# armor_schematic_std.net
KiCad netlist of a schematic drawn in EasyEDA
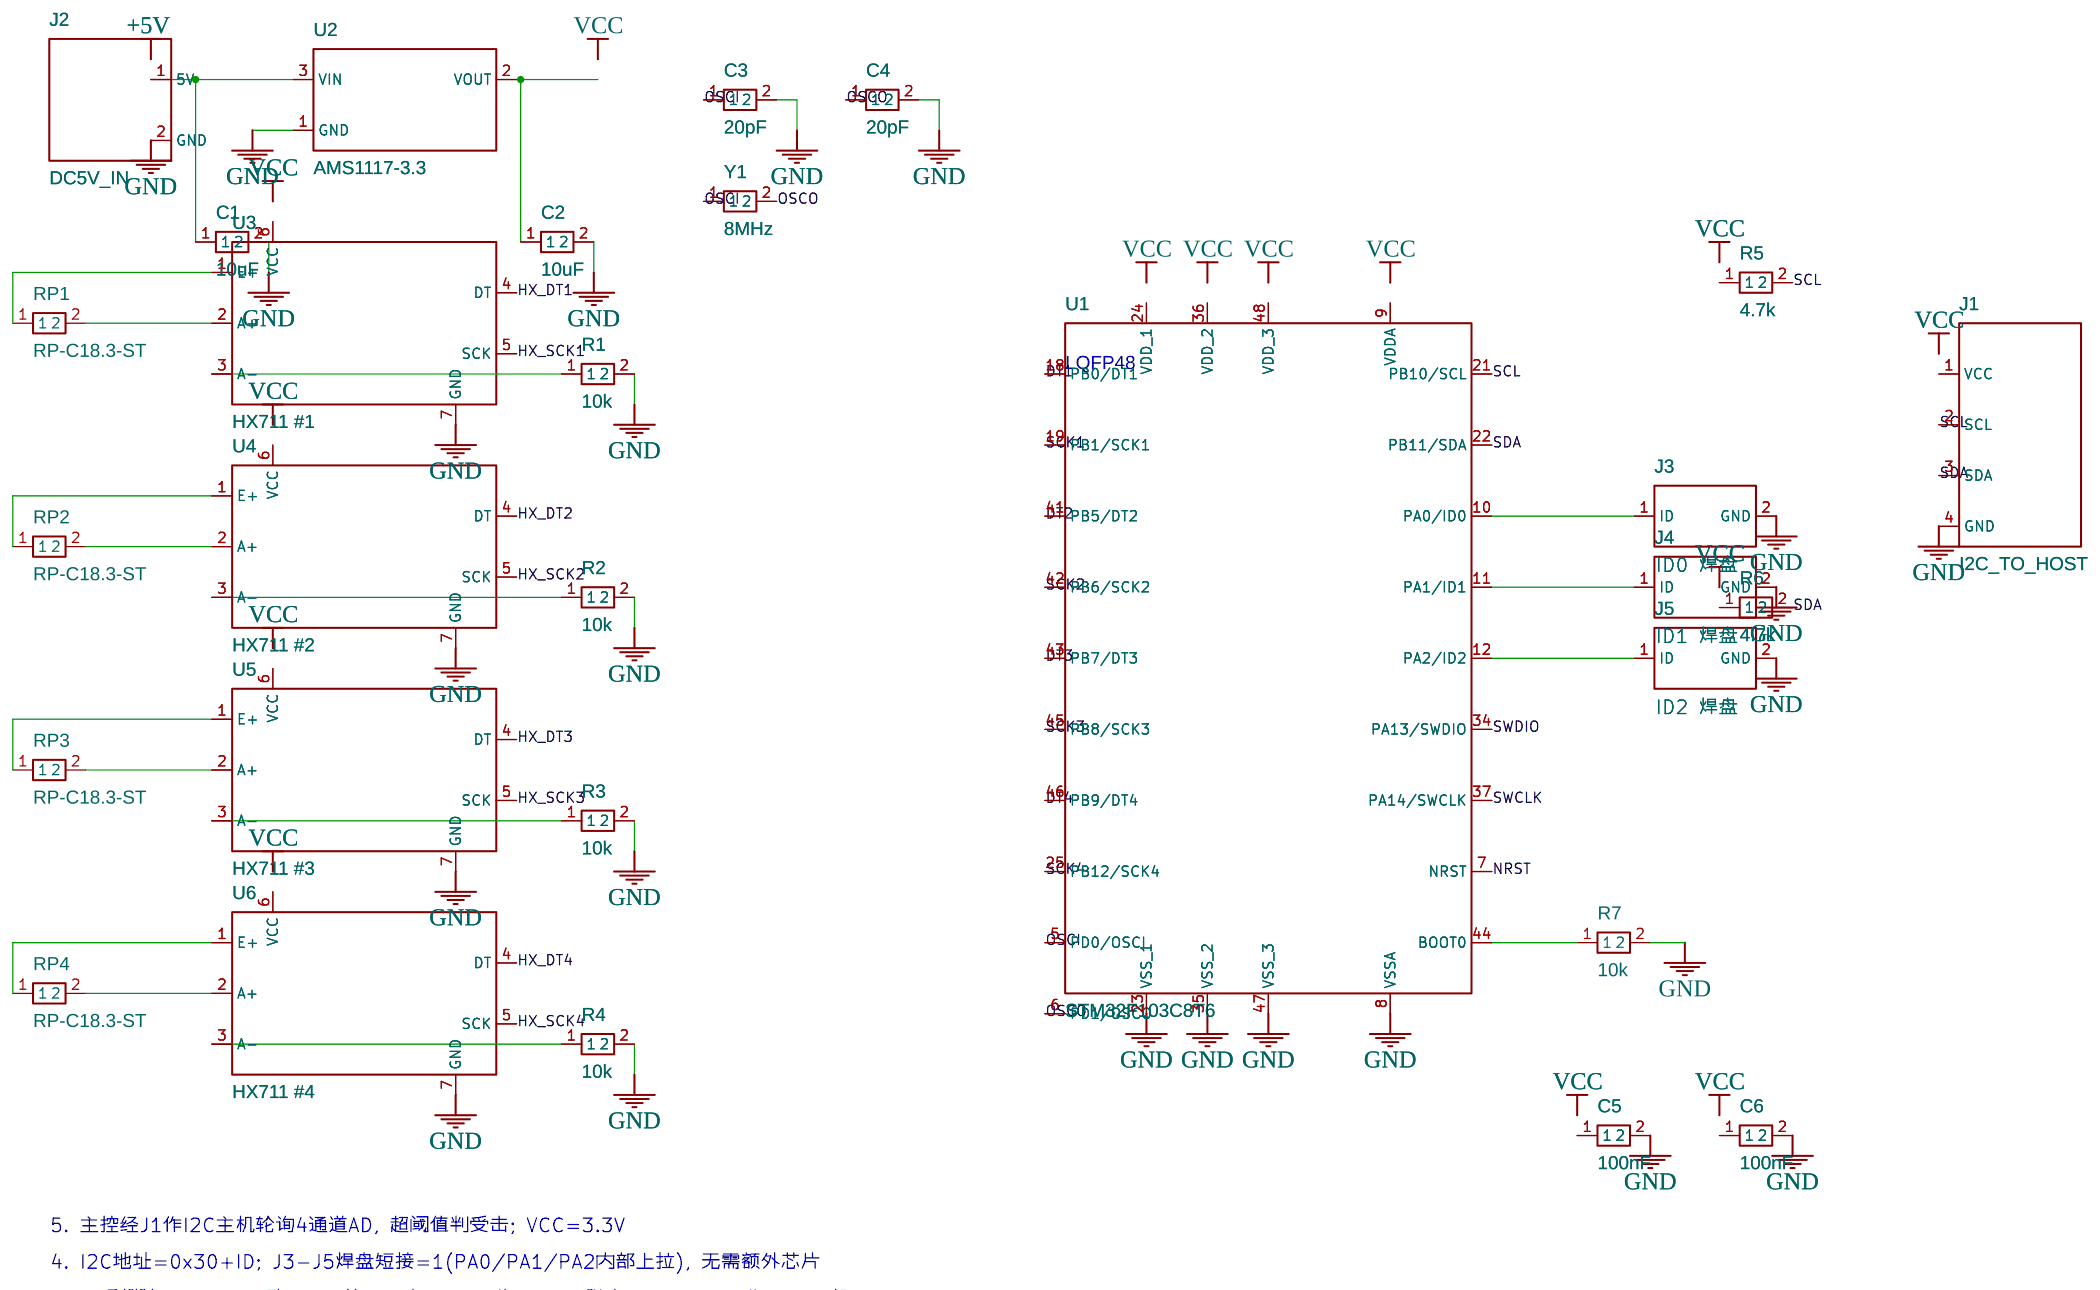
[diagram p0: schematic sheet]

(export (version "E")
  (design (tool "Eeschema 10.0.6"))
  (components
    (comp (ref "C1")
      (value "10uF")
      (fields (field (name "BOM_Manufacturer Part") "CL21A106KAYNNNE"))
      (libsource (lib "") (part "10uF"))
    )
    (comp (ref "C2")
      (value "10uF")
      (fields (field (name "BOM_Manufacturer Part") "CL21A106KAYNNNE"))
      (libsource (lib "") (part "10uF"))
    )
    (comp (ref "C3")
      (value "20pF")
      (fields (field (name "BOM_Manufacturer Part") "CL10C200JB8NNNC"))
      (libsource (lib "") (part "20pF"))
    )
    (comp (ref "C4")
      (value "20pF")
      (fields (field (name "BOM_Manufacturer Part") "CL10C200JB8NNNC"))
      (libsource (lib "") (part "20pF"))
    )
    (comp (ref "C5")
      (value "100nF")
      (fields (field (name "BOM_Manufacturer Part") "CC0603KRX7R9BB104"))
      (libsource (lib "") (part "100nF"))
    )
    (comp (ref "C6")
      (value "100nF")
      (fields (field (name "BOM_Manufacturer Part") "CC0603KRX7R9BB104"))
      (libsource (lib "") (part "100nF"))
    )
    (comp (ref "J1")
      (value "I2C_TO_HOST")
      (fields (field (name "BOM_Manufacturer Part") "PZ254V-11-04P"))
      (libsource (lib "") (part "I2C_TO_HOST"))
    )
    (comp (ref "J2")
      (value "DC5V_IN")
      (fields (field (name "BOM_Manufacturer Part") "PZ254V-11-02P"))
      (libsource (lib "") (part "DC5V_IN"))
    )
    (comp (ref "J3")
      (value "ID0 焊盘")
      (fields (field (name "BOM_Manufacturer Part") "PZ254V-11-02P"))
      (libsource (lib "") (part "ID0 焊盘"))
    )
    (comp (ref "J4")
      (value "ID1 焊盘")
      (fields (field (name "BOM_Manufacturer Part") "PZ254V-11-02P"))
      (libsource (lib "") (part "ID1 焊盘"))
    )
    (comp (ref "J5")
      (value "ID2 焊盘")
      (fields (field (name "BOM_Manufacturer Part") "PZ254V-11-02P"))
      (libsource (lib "") (part "ID2 焊盘"))
    )
    (comp (ref "R1")
      (value "10k")
      (fields (field (name "BOM_Manufacturer Part") "0603WAF1002T5E"))
      (libsource (lib "") (part "10k"))
    )
    (comp (ref "R2")
      (value "10k")
      (fields (field (name "BOM_Manufacturer Part") "0603WAF1002T5E"))
      (libsource (lib "") (part "10k"))
    )
    (comp (ref "R3")
      (value "10k")
      (fields (field (name "BOM_Manufacturer Part") "0603WAF1002T5E"))
      (libsource (lib "") (part "10k"))
    )
    (comp (ref "R4")
      (value "10k")
      (fields (field (name "BOM_Manufacturer Part") "0603WAF1002T5E"))
      (libsource (lib "") (part "10k"))
    )
    (comp (ref "R5")
      (value "4.7k")
      (fields (field (name "BOM_Manufacturer Part") "0603WAF4701T5E"))
      (libsource (lib "") (part "4.7k"))
    )
    (comp (ref "R6")
      (value "4.7k")
      (fields (field (name "BOM_Manufacturer Part") "0603WAF4701T5E"))
      (libsource (lib "") (part "4.7k"))
    )
    (comp (ref "R7")
      (value "10k")
      (fields (field (name "BOM_Manufacturer Part") "0603WAF1002T5E"))
      (libsource (lib "") (part "10k"))
    )
    (comp (ref "RP1") (value "RP-C18.3-ST") (libsource (lib "") (part "RP-C18.3-ST")))
    (comp (ref "RP2") (value "RP-C18.3-ST") (libsource (lib "") (part "RP-C18.3-ST")))
    (comp (ref "RP3") (value "RP-C18.3-ST") (libsource (lib "") (part "RP-C18.3-ST")))
    (comp (ref "RP4") (value "RP-C18.3-ST") (libsource (lib "") (part "RP-C18.3-ST")))
    (comp (ref "U1") (value "STM32F103C8T6") (libsource (lib "") (part "STM32F103C8T6")))
    (comp (ref "U2") (value "AMS1117-3.3") (libsource (lib "") (part "AMS1117-3.3")))
    (comp (ref "U3")
      (value "HX711 #1")
      (fields (field (name "BOM_Manufacturer Part") "HX711 module"))
      (libsource (lib "") (part "HX711 #1"))
    )
    (comp (ref "U4")
      (value "HX711 #2")
      (fields (field (name "BOM_Manufacturer Part") "HX711 module"))
      (libsource (lib "") (part "HX711 #2"))
    )
    (comp (ref "U5")
      (value "HX711 #3")
      (fields (field (name "BOM_Manufacturer Part") "HX711 module"))
      (libsource (lib "") (part "HX711 #3"))
    )
    (comp (ref "U6")
      (value "HX711 #4")
      (fields (field (name "BOM_Manufacturer Part") "HX711 module"))
      (libsource (lib "") (part "HX711 #4"))
    )
    (comp (ref "Y1")
      (value "8MHz")
      (fields (field (name "BOM_Manufacturer Part") "7U08000E10UCG"))
      (libsource (lib "") (part "8MHz"))
    )
  )
  (nets
    (net (code "2") (name "/DT1") (class "Default")
      (node (ref "U1") (pin "18") (pinfunction "PB0/DT1_18") (pintype "unspecified"))
    )
    (net (code "3") (name "/DT2") (class "Default")
      (node (ref "U1") (pin "41") (pinfunction "PB5/DT2_41") (pintype "unspecified"))
    )
    (net (code "4") (name "/DT3") (class "Default")
      (node (ref "U1") (pin "43") (pinfunction "PB7/DT3_43") (pintype "unspecified"))
    )
    (net (code "5") (name "/DT4") (class "Default")
      (node (ref "U1") (pin "46") (pinfunction "PB9/DT4_46") (pintype "unspecified"))
    )
    (net (code "6") (name "/HX_DT1") (class "Default")
      (node (ref "U3") (pin "4") (pinfunction "DT_4") (pintype "unspecified"))
    )
    (net (code "7") (name "/HX_DT2") (class "Default")
      (node (ref "U4") (pin "4") (pinfunction "DT_4") (pintype "unspecified"))
    )
    (net (code "8") (name "/HX_DT3") (class "Default")
      (node (ref "U5") (pin "4") (pinfunction "DT_4") (pintype "unspecified"))
    )
    (net (code "9") (name "/HX_DT4") (class "Default")
      (node (ref "U6") (pin "4") (pinfunction "DT_4") (pintype "unspecified"))
    )
    (net (code "10") (name "/HX_SCK1") (class "Default")
      (node (ref "U3") (pin "5") (pinfunction "SCK_5") (pintype "unspecified"))
    )
    (net (code "11") (name "/HX_SCK2") (class "Default")
      (node (ref "U4") (pin "5") (pinfunction "SCK_5") (pintype "unspecified"))
    )
    (net (code "12") (name "/HX_SCK3") (class "Default")
      (node (ref "U5") (pin "5") (pinfunction "SCK_5") (pintype "unspecified"))
    )
    (net (code "13") (name "/HX_SCK4") (class "Default")
      (node (ref "U6") (pin "5") (pinfunction "SCK_5") (pintype "unspecified"))
    )
    (net (code "14") (name "/NRST") (class "Default")
      (node (ref "U1") (pin "7") (pinfunction "NRST_7") (pintype "unspecified"))
    )
    (net (code "15") (name "/OSCI") (class "Default")
      (node (ref "C3") (pin "1") (pinfunction "1_1") (pintype "unspecified"))
      (node (ref "U1") (pin "5") (pinfunction "PD0/OSCI_5") (pintype "unspecified"))
      (node (ref "Y1") (pin "1") (pinfunction "1_1") (pintype "unspecified"))
    )
    (net (code "16") (name "/OSCO") (class "Default")
      (node (ref "C4") (pin "1") (pinfunction "1_1") (pintype "unspecified"))
      (node (ref "U1") (pin "6") (pinfunction "PD1/OSCO_6") (pintype "unspecified"))
      (node (ref "Y1") (pin "2") (pinfunction "2_2") (pintype "unspecified"))
    )
    (net (code "17") (name "/SCK1") (class "Default")
      (node (ref "U1") (pin "19") (pinfunction "PB1/SCK1_19") (pintype "unspecified"))
    )
    (net (code "18") (name "/SCK2") (class "Default")
      (node (ref "U1") (pin "42") (pinfunction "PB6/SCK2_42") (pintype "unspecified"))
    )
    (net (code "19") (name "/SCK3") (class "Default")
      (node (ref "U1") (pin "45") (pinfunction "PB8/SCK3_45") (pintype "unspecified"))
    )
    (net (code "20") (name "/SCK4") (class "Default")
      (node (ref "U1") (pin "25") (pinfunction "PB12/SCK4_25") (pintype "unspecified"))
    )
    (net (code "21") (name "/SCL") (class "Default")
      (node (ref "J1") (pin "2") (pinfunction "SCL_2") (pintype "unspecified"))
      (node (ref "R5") (pin "2") (pinfunction "2_2") (pintype "unspecified"))
      (node (ref "U1") (pin "21") (pinfunction "PB10/SCL_21") (pintype "unspecified"))
    )
    (net (code "22") (name "/SDA") (class "Default")
      (node (ref "J1") (pin "3") (pinfunction "SDA_3") (pintype "unspecified"))
      (node (ref "R6") (pin "2") (pinfunction "2_2") (pintype "unspecified"))
      (node (ref "U1") (pin "22") (pinfunction "PB11/SDA_22") (pintype "unspecified"))
    )
    (net (code "23") (name "/SWCLK") (class "Default")
      (node (ref "U1") (pin "37") (pinfunction "PA14/SWCLK_37") (pintype "unspecified"))
    )
    (net (code "24") (name "/SWDIO") (class "Default")
      (node (ref "U1") (pin "34") (pinfunction "PA13/SWDIO_34") (pintype "unspecified"))
    )
    (net (code "25") (name "GND") (class "Default")
      (node (ref "C1") (pin "2") (pinfunction "2_2") (pintype "unspecified"))
      (node (ref "C2") (pin "2") (pinfunction "2_2") (pintype "unspecified"))
      (node (ref "C3") (pin "2") (pinfunction "2_2") (pintype "unspecified"))
      (node (ref "C4") (pin "2") (pinfunction "2_2") (pintype "unspecified"))
      (node (ref "C5") (pin "2") (pinfunction "2_2") (pintype "unspecified"))
      (node (ref "C6") (pin "2") (pinfunction "2_2") (pintype "unspecified"))
      (node (ref "J1") (pin "4") (pinfunction "GND_4") (pintype "unspecified"))
      (node (ref "J2") (pin "2") (pinfunction "GND_2") (pintype "unspecified"))
      (node (ref "J3") (pin "2") (pinfunction "GND_2") (pintype "unspecified"))
      (node (ref "J4") (pin "2") (pinfunction "GND_2") (pintype "unspecified"))
      (node (ref "J5") (pin "2") (pinfunction "GND_2") (pintype "unspecified"))
      (node (ref "R1") (pin "2") (pinfunction "2_2") (pintype "unspecified"))
      (node (ref "R2") (pin "2") (pinfunction "2_2") (pintype "unspecified"))
      (node (ref "R3") (pin "2") (pinfunction "2_2") (pintype "unspecified"))
      (node (ref "R4") (pin "2") (pinfunction "2_2") (pintype "unspecified"))
      (node (ref "R7") (pin "2") (pinfunction "2_2") (pintype "unspecified"))
      (node (ref "U1") (pin "23") (pinfunction "VSS_1_23") (pintype "unspecified"))
      (node (ref "U1") (pin "35") (pinfunction "VSS_2_35") (pintype "unspecified"))
      (node (ref "U1") (pin "47") (pinfunction "VSS_3_47") (pintype "unspecified"))
      (node (ref "U1") (pin "8") (pinfunction "VSSA_8") (pintype "unspecified"))
      (node (ref "U2") (pin "1") (pinfunction "GND_1") (pintype "unspecified"))
      (node (ref "U3") (pin "7") (pinfunction "GND_7") (pintype "unspecified"))
      (node (ref "U4") (pin "7") (pinfunction "GND_7") (pintype "unspecified"))
      (node (ref "U5") (pin "7") (pinfunction "GND_7") (pintype "unspecified"))
      (node (ref "U6") (pin "7") (pinfunction "GND_7") (pintype "unspecified"))
    )
    (net (code "26") (name "Net-(J2-5V)") (class "Default")
      (node (ref "C1") (pin "1") (pinfunction "1_1") (pintype "unspecified"))
      (node (ref "J2") (pin "1") (pinfunction "5V_1") (pintype "unspecified"))
      (node (ref "U2") (pin "3") (pinfunction "VIN_3") (pintype "unspecified"))
    )
    (net (code "27") (name "Net-(J3-ID)") (class "Default")
      (node (ref "J3") (pin "1") (pinfunction "ID_1") (pintype "unspecified"))
      (node (ref "U1") (pin "10") (pinfunction "PA0/ID0_10") (pintype "unspecified"))
    )
    (net (code "28") (name "Net-(J4-ID)") (class "Default")
      (node (ref "J4") (pin "1") (pinfunction "ID_1") (pintype "unspecified"))
      (node (ref "U1") (pin "11") (pinfunction "PA1/ID1_11") (pintype "unspecified"))
    )
    (net (code "29") (name "Net-(J5-ID)") (class "Default")
      (node (ref "J5") (pin "1") (pinfunction "ID_1") (pintype "unspecified"))
      (node (ref "U1") (pin "12") (pinfunction "PA2/ID2_12") (pintype "unspecified"))
    )
    (net (code "30") (name "Net-(U1-BOOT0)") (class "Default")
      (node (ref "R7") (pin "1") (pinfunction "1_1") (pintype "unspecified"))
      (node (ref "U1") (pin "44") (pinfunction "BOOT0_44") (pintype "unspecified"))
    )
    (net (code "31") (name "Net-(U2-VOUT)") (class "Default")
      (node (ref "C2") (pin "1") (pinfunction "1_1") (pintype "unspecified"))
      (node (ref "U2") (pin "2") (pinfunction "VOUT_2") (pintype "unspecified"))
    )
    (net (code "32") (name "Net-(U3-A+)") (class "Default")
      (node (ref "RP1") (pin "2") (pinfunction "2_2") (pintype "unspecified"))
      (node (ref "U3") (pin "2") (pinfunction "A+_2") (pintype "unspecified"))
    )
    (net (code "33") (name "Net-(U3-A-)") (class "Default")
      (node (ref "R1") (pin "1") (pinfunction "1_1") (pintype "unspecified"))
      (node (ref "U3") (pin "3") (pinfunction "A-_3") (pintype "unspecified"))
    )
    (net (code "34") (name "Net-(U3-E+)") (class "Default")
      (node (ref "RP1") (pin "1") (pinfunction "1_1") (pintype "unspecified"))
      (node (ref "U3") (pin "1") (pinfunction "E+_1") (pintype "unspecified"))
    )
    (net (code "35") (name "Net-(U4-A+)") (class "Default")
      (node (ref "RP2") (pin "2") (pinfunction "2_2") (pintype "unspecified"))
      (node (ref "U4") (pin "2") (pinfunction "A+_2") (pintype "unspecified"))
    )
    (net (code "36") (name "Net-(U4-A-)") (class "Default")
      (node (ref "R2") (pin "1") (pinfunction "1_1") (pintype "unspecified"))
      (node (ref "U4") (pin "3") (pinfunction "A-_3") (pintype "unspecified"))
    )
    (net (code "37") (name "Net-(U4-E+)") (class "Default")
      (node (ref "RP2") (pin "1") (pinfunction "1_1") (pintype "unspecified"))
      (node (ref "U4") (pin "1") (pinfunction "E+_1") (pintype "unspecified"))
    )
    (net (code "38") (name "Net-(U5-A+)") (class "Default")
      (node (ref "RP3") (pin "2") (pinfunction "2_2") (pintype "unspecified"))
      (node (ref "U5") (pin "2") (pinfunction "A+_2") (pintype "unspecified"))
    )
    (net (code "39") (name "Net-(U5-A-)") (class "Default")
      (node (ref "R3") (pin "1") (pinfunction "1_1") (pintype "unspecified"))
      (node (ref "U5") (pin "3") (pinfunction "A-_3") (pintype "unspecified"))
    )
    (net (code "40") (name "Net-(U5-E+)") (class "Default")
      (node (ref "RP3") (pin "1") (pinfunction "1_1") (pintype "unspecified"))
      (node (ref "U5") (pin "1") (pinfunction "E+_1") (pintype "unspecified"))
    )
    (net (code "41") (name "Net-(U6-A+)") (class "Default")
      (node (ref "RP4") (pin "2") (pinfunction "2_2") (pintype "unspecified"))
      (node (ref "U6") (pin "2") (pinfunction "A+_2") (pintype "unspecified"))
    )
    (net (code "42") (name "Net-(U6-A-)") (class "Default")
      (node (ref "R4") (pin "1") (pinfunction "1_1") (pintype "unspecified"))
      (node (ref "U6") (pin "3") (pinfunction "A-_3") (pintype "unspecified"))
    )
    (net (code "43") (name "Net-(U6-E+)") (class "Default")
      (node (ref "RP4") (pin "1") (pinfunction "1_1") (pintype "unspecified"))
      (node (ref "U6") (pin "1") (pinfunction "E+_1") (pintype "unspecified"))
    )
    (net (code "45") (name "unconnected-(C5-Pad1)") (class "Default")
      (node (ref "C5") (pin "1") (pinfunction "1_1") (pintype "unspecified"))
    )
    (net (code "46") (name "unconnected-(C6-Pad1)") (class "Default")
      (node (ref "C6") (pin "1") (pinfunction "1_1") (pintype "unspecified"))
    )
    (net (code "47") (name "unconnected-(J1-VCC-Pad1)") (class "Default")
      (node (ref "J1") (pin "1") (pinfunction "VCC_1") (pintype "unspecified"))
    )
    (net (code "48") (name "unconnected-(R5-Pad1)") (class "Default")
      (node (ref "R5") (pin "1") (pinfunction "1_1") (pintype "unspecified"))
    )
    (net (code "49") (name "unconnected-(R6-Pad1)") (class "Default")
      (node (ref "R6") (pin "1") (pinfunction "1_1") (pintype "unspecified"))
    )
    (net (code "50") (name "unconnected-(U1-VDDA-Pad9)") (class "Default")
      (node (ref "U1") (pin "9") (pinfunction "VDDA_9") (pintype "unspecified"))
    )
    (net (code "51") (name "unconnected-(U1-VDD_1-Pad24)") (class "Default")
      (node (ref "U1") (pin "24") (pinfunction "VDD_1_24") (pintype "unspecified"))
    )
    (net (code "52") (name "unconnected-(U1-VDD_2-Pad36)") (class "Default")
      (node (ref "U1") (pin "36") (pinfunction "VDD_2_36") (pintype "unspecified"))
    )
    (net (code "53") (name "unconnected-(U1-VDD_3-Pad48)") (class "Default")
      (node (ref "U1") (pin "48") (pinfunction "VDD_3_48") (pintype "unspecified"))
    )
    (net (code "54") (name "unconnected-(U3-VCC-Pad6)") (class "Default")
      (node (ref "U3") (pin "6") (pinfunction "VCC_6") (pintype "unspecified"))
    )
    (net (code "55") (name "unconnected-(U4-VCC-Pad6)") (class "Default")
      (node (ref "U4") (pin "6") (pinfunction "VCC_6") (pintype "unspecified"))
    )
    (net (code "56") (name "unconnected-(U5-VCC-Pad6)") (class "Default")
      (node (ref "U5") (pin "6") (pinfunction "VCC_6") (pintype "unspecified"))
    )
    (net (code "57") (name "unconnected-(U6-VCC-Pad6)") (class "Default")
      (node (ref "U6") (pin "6") (pinfunction "VCC_6") (pintype "unspecified"))
    )
  )
)
